# Un_51_V3_0.net
KiCad netlist of a schematic drawn in EAGLE
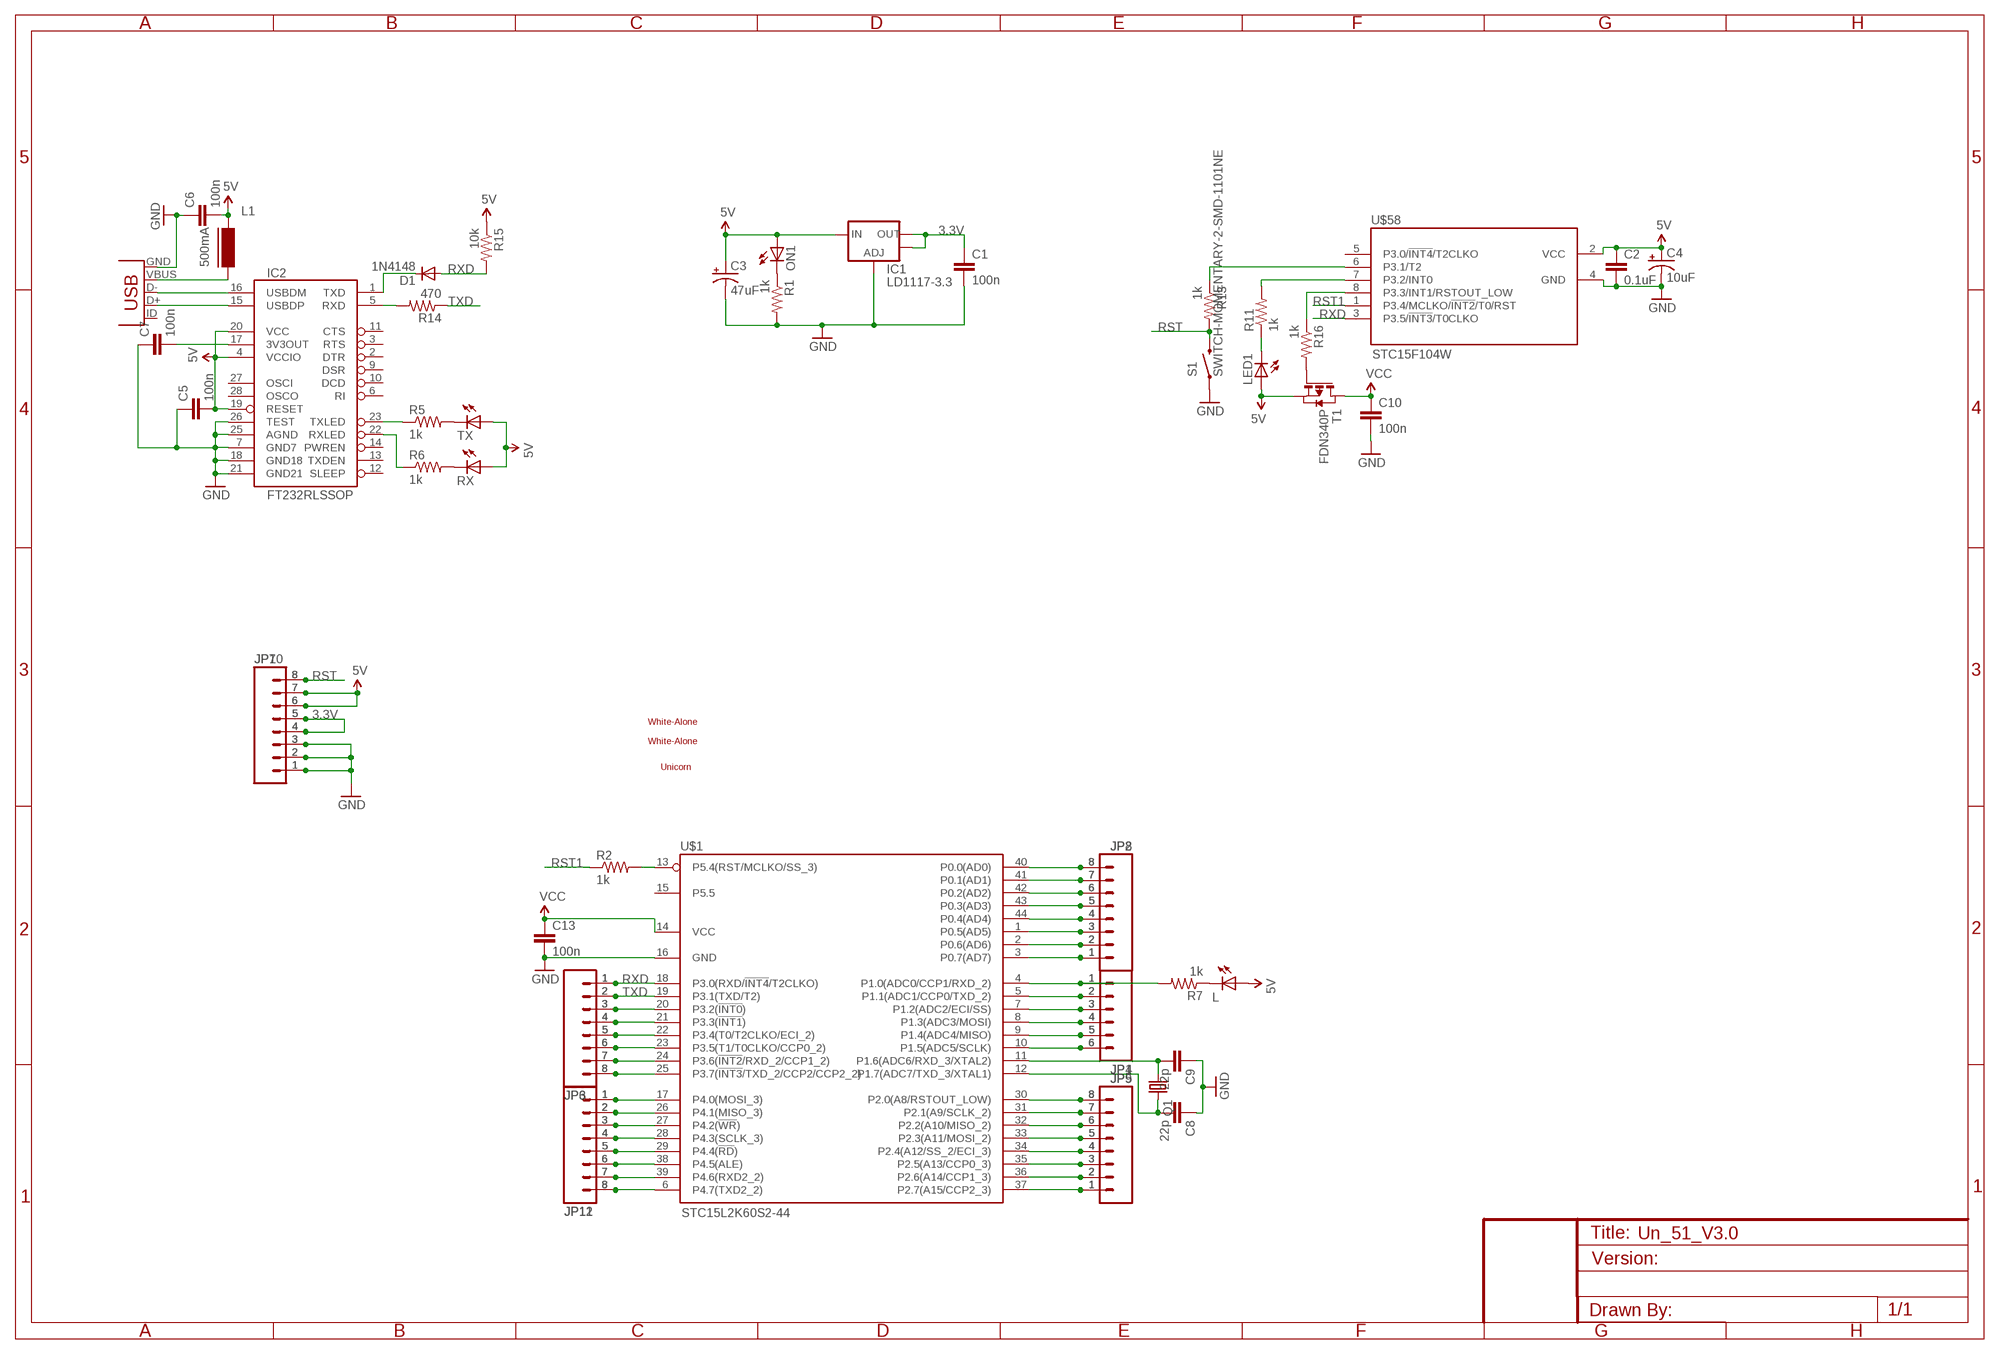
[diagram p0: schematic, sheet 1]

(export (version "E")
  (design (tool "Eeschema 10.0.6"))
  (components
    (comp (ref "C1")
      (value "100n")
      (footprint "eagle-import:0603-CAP")
      (libsource (lib "eagle-import") (part "2SparkFun_CAP0603-CAP"))
    )
    (comp (ref "C2")
      (value "0.1uF")
      (footprint "eagle-import:0603-CAP")
      (libsource (lib "eagle-import") (part "2SparkFun_CAP0603-CAP"))
    )
    (comp (ref "C3")
      (value "47uF")
      (footprint "eagle-import:PANASONIC_D")
      (libsource (lib "eagle-import") (part "CAP_POLD"))
    )
    (comp (ref "C4")
      (value "10uF")
      (footprint "eagle-import:EIA3216")
      (libsource (lib "eagle-import") (part "CAP_POL1206"))
    )
    (comp (ref "C5")
      (value "100n")
      (footprint "eagle-import:0603-CAP")
      (libsource (lib "eagle-import") (part "2SparkFun_CAP0603-CAP"))
    )
    (comp (ref "C6")
      (value "100n")
      (footprint "eagle-import:0603-CAP")
      (libsource (lib "eagle-import") (part "2SparkFun_CAP0603-CAP"))
    )
    (comp (ref "C7")
      (value "100n")
      (footprint "eagle-import:0603-CAP")
      (libsource (lib "eagle-import") (part "2SparkFun_CAP0603-CAP"))
    )
    (comp (ref "C8")
      (value "22p")
      (footprint "eagle-import:0603-CAP")
      (libsource (lib "eagle-import") (part "2SparkFun_CAP0603-CAP"))
    )
    (comp (ref "C9")
      (value "22p")
      (footprint "eagle-import:0603-CAP")
      (libsource (lib "eagle-import") (part "2SparkFun_CAP0603-CAP"))
    )
    (comp (ref "C10")
      (value "100n")
      (footprint "eagle-import:0603-CAP")
      (libsource (lib "eagle-import") (part "2SparkFun_CAP0603-CAP"))
    )
    (comp (ref "C13")
      (value "100n")
      (footprint "eagle-import:0603-CAP")
      (libsource (lib "eagle-import") (part "CAP0603-CAP"))
    )
    (comp (ref "D1")
      (value "1N4148")
      (footprint "eagle-import:SOD-323")
      (libsource (lib "eagle-import") (part "DIODESOD"))
    )
    (comp (ref "IC1")
      (value "LD1117-3.3")
      (footprint "eagle-import:SOT223")
      (libsource (lib "eagle-import") (part "V_REG_LM1117SOT223"))
    )
    (comp (ref "IC2")
      (value "FT232RLSSOP")
      (footprint "eagle-import:SSOP28DB")
      (libsource (lib "eagle-import") (part "FT232RLSSOP"))
    )
    (comp (ref "JP1")
      (value "M06SIP")
      (footprint "eagle-import:1X06")
      (libsource (lib "eagle-import") (part "M06SIP"))
    )
    (comp (ref "JP2")
      (value "M08")
      (footprint "eagle-import:1X08")
      (libsource (lib "eagle-import") (part "M08"))
    )
    (comp (ref "JP3")
      (value "M08")
      (footprint "eagle-import:1X08")
      (libsource (lib "eagle-import") (part "M08"))
    )
    (comp (ref "JP4")
      (value "M06SIP")
      (footprint "eagle-import:1X06")
      (libsource (lib "eagle-import") (part "M06SIP"))
    )
    (comp (ref "JP5")
      (value "M08")
      (footprint "eagle-import:1X08")
      (libsource (lib "eagle-import") (part "M08"))
    )
    (comp (ref "JP6")
      (value "M08")
      (footprint "eagle-import:1X08")
      (libsource (lib "eagle-import") (part "M08"))
    )
    (comp (ref "JP7")
      (value "M08")
      (footprint "eagle-import:1X08")
      (libsource (lib "eagle-import") (part "M08"))
    )
    (comp (ref "JP8")
      (value "M08")
      (footprint "eagle-import:1X08")
      (libsource (lib "eagle-import") (part "M08"))
    )
    (comp (ref "JP9")
      (value "M08")
      (footprint "eagle-import:1X08")
      (libsource (lib "eagle-import") (part "M08"))
    )
    (comp (ref "JP10")
      (value "M08")
      (footprint "eagle-import:1X08")
      (libsource (lib "eagle-import") (part "M08"))
    )
    (comp (ref "JP11")
      (value "M08")
      (footprint "eagle-import:1X08")
      (libsource (lib "eagle-import") (part "M08"))
    )
    (comp (ref "JP12")
      (value "M08")
      (footprint "eagle-import:1X08")
      (libsource (lib "eagle-import") (part "M08"))
    )
    (comp (ref "L")
      (value "LED0805")
      (footprint "eagle-import:LED-0805")
      (libsource (lib "eagle-import") (part "LED0805"))
    )
    (comp (ref "L1")
      (value "500mA")
      (footprint "eagle-import:FB805")
      (libsource (lib "eagle-import") (part "FERRITE-0805"))
    )
    (comp (ref "LED1")
      (value "LED0805")
      (footprint "eagle-import:LED-0805")
      (libsource (lib "eagle-import") (part "2SparkFun_LED0805"))
    )
    (comp (ref "ON1")
      (value "LED0805")
      (footprint "eagle-import:LED-0805")
      (libsource (lib "eagle-import") (part "LED0805"))
    )
    (comp (ref "Q1")
      (value "CRYSTALHC49US")
      (footprint "eagle-import:HC49US")
      (libsource (lib "eagle-import") (part "CRYSTALHC49US"))
    )
    (comp (ref "R1")
      (value "1k")
      (footprint "eagle-import:0603-RES")
      (libsource (lib "eagle-import") (part "RESISTOR0603-RES"))
    )
    (comp (ref "R2")
      (value "1k")
      (footprint "eagle-import:0603-RES")
      (libsource (lib "eagle-import") (part "RESISTOR0603-RES"))
    )
    (comp (ref "R5")
      (value "1k")
      (footprint "eagle-import:0603-RES")
      (libsource (lib "eagle-import") (part "RESISTOR0603-RES"))
    )
    (comp (ref "R6")
      (value "1k")
      (footprint "eagle-import:0603-RES")
      (libsource (lib "eagle-import") (part "RESISTOR0603-RES"))
    )
    (comp (ref "R7")
      (value "1k")
      (footprint "eagle-import:0603-RES")
      (libsource (lib "eagle-import") (part "RESISTOR0603-RES"))
    )
    (comp (ref "R11")
      (value "1k")
      (footprint "eagle-import:0603-RES")
      (libsource (lib "eagle-import") (part "RESISTOR0603-RES"))
    )
    (comp (ref "R13")
      (value "1k")
      (footprint "eagle-import:0603-RES")
      (libsource (lib "eagle-import") (part "RESISTOR0603-RES"))
    )
    (comp (ref "R14")
      (value "470")
      (footprint "eagle-import:0603-RES")
      (libsource (lib "eagle-import") (part "RESISTOR0603-RES"))
    )
    (comp (ref "R15")
      (value "10k")
      (footprint "eagle-import:0603-RES")
      (libsource (lib "eagle-import") (part "RESISTOR0603-RES"))
    )
    (comp (ref "R16")
      (value "1k")
      (footprint "eagle-import:0603-RES")
      (libsource (lib "eagle-import") (part "RESISTOR0603-RES"))
    )
    (comp (ref "RX")
      (value "LED0805")
      (footprint "eagle-import:LED-0805")
      (libsource (lib "eagle-import") (part "LED0805"))
    )
    (comp (ref "S1")
      (value "SWITCH-MOMENTARY-2-SMD-1101NE")
      (footprint "eagle-import:TACTILE-SWITCH-1101NE")
      (libsource (lib "eagle-import") (part "SWITCH-MOMENTARY-2-SMD-1101NE"))
    )
    (comp (ref "T1")
      (value "FDN340P")
      (footprint "eagle-import:SOT-23")
      (libsource (lib "eagle-import") (part "PMOSSOT23"))
    )
    (comp (ref "TX")
      (value "LED0805")
      (footprint "eagle-import:LED-0805")
      (libsource (lib "eagle-import") (part "LED0805"))
    )
    (comp (ref "U$1")
      (value "STC15L2K60S2-44")
      (footprint "eagle-import:TQFP44")
      (libsource (lib "eagle-import") (part "STC15L2K60S2-44"))
    )
    (comp (ref "U$3")
      (value "UNICORN_2")
      (footprint "eagle-import:UNICORN_2")
      (libsource (lib "eagle-import") (part "UNICORN_2"))
    )
    (comp (ref "U$7")
      (value "WHITE-ALONE_0")
      (footprint "eagle-import:WHITE-ALONE_0")
      (libsource (lib "eagle-import") (part "WHITE-ALONE_0"))
    )
    (comp (ref "U$11")
      (value "WHITE-ALONE_0")
      (footprint "eagle-import:WHITE-ALONE_0")
      (libsource (lib "eagle-import") (part "WHITE-ALONE_0"))
    )
    (comp (ref "U$58")
      (value "STC15F104W")
      (footprint "eagle-import:SO08")
      (libsource (lib "eagle-import") (part "STC15F104W"))
    )
    (comp (ref "X2")
      (value "USBSMD")
      (footprint "eagle-import:USB-MINIB")
      (libsource (lib "eagle-import") (part "USBSMD"))
    )
  )
  (nets
    (net (code "1") (name "/3.3V") (class "Default")
      (node (ref "C1") (pin "1") (pinfunction "1_1") (pintype "passive"))
      (node (ref "IC1") (pin "2") (pinfunction "OUT_2") (pintype "output"))
      (node (ref "IC1") (pin "4") (pinfunction "OUT_4") (pintype "output"))
      (node (ref "JP10") (pin "4") (pinfunction "4_4") (pintype "passive"))
      (node (ref "JP10") (pin "5") (pinfunction "5_5") (pintype "passive"))
      (node (ref "JP7") (pin "4") (pinfunction "4_4") (pintype "passive"))
      (node (ref "JP7") (pin "5") (pinfunction "5_5") (pintype "passive"))
    )
    (net (code "2") (name "/RST") (class "Default")
      (node (ref "JP10") (pin "8") (pinfunction "8_8") (pintype "passive"))
      (node (ref "JP7") (pin "8") (pinfunction "8_8") (pintype "passive"))
      (node (ref "R13") (pin "2") (pinfunction "2_2") (pintype "passive"))
      (node (ref "S1") (pin "P$2") (pinfunction "2_P$2") (pintype "passive"))
    )
    (net (code "3") (name "/RST1") (class "Default")
      (node (ref "R2") (pin "1") (pinfunction "1_1") (pintype "passive"))
      (node (ref "U$58") (pin "1") (pinfunction "P3.4/MCLKO/~{INT2}/T0/RST_1") (pintype "bidirectional"))
    )
    (net (code "4") (name "/RXD") (class "Default")
      (node (ref "D1") (pin "2") (pinfunction "A_2") (pintype "passive"))
      (node (ref "JP3") (pin "1") (pinfunction "1_1") (pintype "passive"))
      (node (ref "JP6") (pin "1") (pinfunction "1_1") (pintype "passive"))
      (node (ref "R15") (pin "2") (pinfunction "2_2") (pintype "passive"))
      (node (ref "U$1") (pin "18") (pinfunction "P3.0(RXD/~{INT4}/T2CLKO)_18") (pintype "bidirectional"))
      (node (ref "U$58") (pin "3") (pinfunction "P3.5/~{INT3}/T0CLKO_3") (pintype "bidirectional"))
    )
    (net (code "5") (name "/TXD") (class "Default")
      (node (ref "JP3") (pin "2") (pinfunction "2_2") (pintype "passive"))
      (node (ref "JP6") (pin "2") (pinfunction "2_2") (pintype "passive"))
      (node (ref "R14") (pin "1") (pinfunction "1_1") (pintype "passive"))
      (node (ref "U$1") (pin "19") (pinfunction "P3.1(TXD/T2)_19") (pintype "bidirectional"))
    )
    (net (code "6") (name "5V") (class "Default")
      (node (ref "C2") (pin "1") (pinfunction "1_1") (pintype "passive"))
      (node (ref "C3") (pin "+") (pinfunction "+_+") (pintype "passive"))
      (node (ref "C4") (pin "A") (pinfunction "+_A") (pintype "passive"))
      (node (ref "C5") (pin "2") (pinfunction "2_2") (pintype "passive"))
      (node (ref "C6") (pin "2") (pinfunction "2_2") (pintype "passive"))
      (node (ref "IC1") (pin "3") (pinfunction "IN_3") (pintype "input"))
      (node (ref "IC2") (pin "19") (pinfunction "RESET_19") (pintype "input"))
      (node (ref "IC2") (pin "20") (pinfunction "VCC_20") (pintype "power_in"))
      (node (ref "IC2") (pin "4") (pinfunction "VCCIO_4") (pintype "power_in"))
      (node (ref "JP10") (pin "6") (pinfunction "6_6") (pintype "passive"))
      (node (ref "JP10") (pin "7") (pinfunction "7_7") (pintype "passive"))
      (node (ref "JP7") (pin "6") (pinfunction "6_6") (pintype "passive"))
      (node (ref "JP7") (pin "7") (pinfunction "7_7") (pintype "passive"))
      (node (ref "L") (pin "1") (pinfunction "A_1") (pintype "passive"))
      (node (ref "L1") (pin "1") (pinfunction "1_1") (pintype "passive"))
      (node (ref "LED1") (pin "1") (pinfunction "A_1") (pintype "passive"))
      (node (ref "ON1") (pin "1") (pinfunction "A_1") (pintype "passive"))
      (node (ref "R15") (pin "1") (pinfunction "1_1") (pintype "passive"))
      (node (ref "RX") (pin "1") (pinfunction "A_1") (pintype "passive"))
      (node (ref "T1") (pin "2") (pinfunction "S_2") (pintype "passive"))
      (node (ref "TX") (pin "1") (pinfunction "A_1") (pintype "passive"))
      (node (ref "U$58") (pin "2") (pinfunction "VCC_2") (pintype "bidirectional"))
    )
    (net (code "7") (name "GND") (class "Default")
      (node (ref "C1") (pin "2") (pinfunction "2_2") (pintype "passive"))
      (node (ref "C10") (pin "2") (pinfunction "2_2") (pintype "passive"))
      (node (ref "C13") (pin "2") (pinfunction "2_2") (pintype "passive"))
      (node (ref "C2") (pin "2") (pinfunction "2_2") (pintype "passive"))
      (node (ref "C3") (pin "-") (pinfunction "-_-") (pintype "passive"))
      (node (ref "C4") (pin "C") (pinfunction "-_C") (pintype "passive"))
      (node (ref "C5") (pin "1") (pinfunction "1_1") (pintype "passive"))
      (node (ref "C6") (pin "1") (pinfunction "1_1") (pintype "passive"))
      (node (ref "C7") (pin "1") (pinfunction "1_1") (pintype "passive"))
      (node (ref "C8") (pin "1") (pinfunction "1_1") (pintype "passive"))
      (node (ref "C9") (pin "1") (pinfunction "1_1") (pintype "passive"))
      (node (ref "IC1") (pin "1") (pinfunction "ADJ_1") (pintype "input"))
      (node (ref "IC2") (pin "18") (pinfunction "GND18_18") (pintype "power_in"))
      (node (ref "IC2") (pin "21") (pinfunction "GND21_21") (pintype "power_in"))
      (node (ref "IC2") (pin "25") (pinfunction "AGND_25") (pintype "power_in"))
      (node (ref "IC2") (pin "26") (pinfunction "TEST_26") (pintype "input"))
      (node (ref "IC2") (pin "7") (pinfunction "GND7_7") (pintype "power_in"))
      (node (ref "JP10") (pin "1") (pinfunction "1_1") (pintype "passive"))
      (node (ref "JP10") (pin "2") (pinfunction "2_2") (pintype "passive"))
      (node (ref "JP10") (pin "3") (pinfunction "3_3") (pintype "passive"))
      (node (ref "JP7") (pin "1") (pinfunction "1_1") (pintype "passive"))
      (node (ref "JP7") (pin "2") (pinfunction "2_2") (pintype "passive"))
      (node (ref "JP7") (pin "3") (pinfunction "3_3") (pintype "passive"))
      (node (ref "R1") (pin "2") (pinfunction "2_2") (pintype "passive"))
      (node (ref "S1") (pin "P$1") (pinfunction "1_P$1") (pintype "passive"))
      (node (ref "U$1") (pin "16") (pinfunction "GND_16") (pintype "bidirectional"))
      (node (ref "U$58") (pin "4") (pinfunction "GND_4") (pintype "bidirectional"))
      (node (ref "X2") (pin "GND") (pinfunction "GND_GND") (pintype "bidirectional"))
    )
    (net (code "8") (name "Net-(D1-C)") (class "Default")
      (node (ref "D1") (pin "1") (pinfunction "C_1") (pintype "passive"))
      (node (ref "IC2") (pin "1") (pinfunction "TXD_1") (pintype "output"))
    )
    (net (code "9") (name "Net-(IC2-3V3OUT)") (class "Default")
      (node (ref "C7") (pin "2") (pinfunction "2_2") (pintype "passive"))
      (node (ref "IC2") (pin "17") (pinfunction "3V3OUT_17") (pintype "output"))
    )
    (net (code "10") (name "Net-(IC2-RXD)") (class "Default")
      (node (ref "IC2") (pin "5") (pinfunction "RXD_5") (pintype "input"))
      (node (ref "R14") (pin "2") (pinfunction "2_2") (pintype "passive"))
    )
    (net (code "11") (name "Net-(IC2-RXLED)") (class "Default")
      (node (ref "IC2") (pin "22") (pinfunction "RXLED_22") (pintype "input"))
      (node (ref "R6") (pin "1") (pinfunction "1_1") (pintype "passive"))
    )
    (net (code "12") (name "Net-(IC2-TXLED)") (class "Default")
      (node (ref "IC2") (pin "23") (pinfunction "TXLED_23") (pintype "input"))
      (node (ref "R5") (pin "1") (pinfunction "1_1") (pintype "passive"))
    )
    (net (code "13") (name "Net-(IC2-USBDM)") (class "Default")
      (node (ref "IC2") (pin "16") (pinfunction "USBDM_16") (pintype "bidirectional"))
      (node (ref "X2") (pin "D-") (pinfunction "D-_D-") (pintype "bidirectional"))
    )
    (net (code "14") (name "Net-(IC2-USBDP)") (class "Default")
      (node (ref "IC2") (pin "15") (pinfunction "USBDP_15") (pintype "bidirectional"))
      (node (ref "X2") (pin "D+") (pinfunction "D+_D+") (pintype "bidirectional"))
    )
    (net (code "15") (name "Net-(L-C)") (class "Default")
      (node (ref "L") (pin "2") (pinfunction "C_2") (pintype "passive"))
      (node (ref "R7") (pin "1") (pinfunction "1_1") (pintype "passive"))
    )
    (net (code "16") (name "Net-(L1-Pad2)") (class "Default")
      (node (ref "L1") (pin "2") (pinfunction "2_2") (pintype "passive"))
      (node (ref "X2") (pin "VBUS") (pinfunction "VBUS_VBUS") (pintype "bidirectional"))
    )
    (net (code "17") (name "Net-(LED1-C)") (class "Default")
      (node (ref "LED1") (pin "2") (pinfunction "C_2") (pintype "passive"))
      (node (ref "R11") (pin "1") (pinfunction "1_1") (pintype "passive"))
    )
    (net (code "18") (name "Net-(ON1-C)") (class "Default")
      (node (ref "ON1") (pin "2") (pinfunction "C_2") (pintype "passive"))
      (node (ref "R1") (pin "1") (pinfunction "1_1") (pintype "passive"))
    )
    (net (code "19") (name "Net-(RX-C)") (class "Default")
      (node (ref "R6") (pin "2") (pinfunction "2_2") (pintype "passive"))
      (node (ref "RX") (pin "2") (pinfunction "C_2") (pintype "passive"))
    )
    (net (code "20") (name "Net-(T1-G)") (class "Default")
      (node (ref "R16") (pin "2") (pinfunction "2_2") (pintype "passive"))
      (node (ref "T1") (pin "3") (pinfunction "G_3") (pintype "passive"))
    )
    (net (code "21") (name "Net-(TX-C)") (class "Default")
      (node (ref "R5") (pin "2") (pinfunction "2_2") (pintype "passive"))
      (node (ref "TX") (pin "2") (pinfunction "C_2") (pintype "passive"))
    )
    (net (code "22") (name "Net-(U$1-P0.0(AD0))") (class "Default")
      (node (ref "JP2") (pin "8") (pinfunction "8_8") (pintype "passive"))
      (node (ref "JP8") (pin "8") (pinfunction "8_8") (pintype "passive"))
      (node (ref "U$1") (pin "40") (pinfunction "P0.0(AD0)_40") (pintype "bidirectional"))
    )
    (net (code "23") (name "Net-(U$1-P0.1(AD1))") (class "Default")
      (node (ref "JP2") (pin "7") (pinfunction "7_7") (pintype "passive"))
      (node (ref "JP8") (pin "7") (pinfunction "7_7") (pintype "passive"))
      (node (ref "U$1") (pin "41") (pinfunction "P0.1(AD1)_41") (pintype "bidirectional"))
    )
    (net (code "24") (name "Net-(U$1-P0.2(AD2))") (class "Default")
      (node (ref "JP2") (pin "6") (pinfunction "6_6") (pintype "passive"))
      (node (ref "JP8") (pin "6") (pinfunction "6_6") (pintype "passive"))
      (node (ref "U$1") (pin "42") (pinfunction "P0.2(AD2)_42") (pintype "bidirectional"))
    )
    (net (code "25") (name "Net-(U$1-P0.3(AD3))") (class "Default")
      (node (ref "JP2") (pin "5") (pinfunction "5_5") (pintype "passive"))
      (node (ref "JP8") (pin "5") (pinfunction "5_5") (pintype "passive"))
      (node (ref "U$1") (pin "43") (pinfunction "P0.3(AD3)_43") (pintype "bidirectional"))
    )
    (net (code "26") (name "Net-(U$1-P0.4(AD4))") (class "Default")
      (node (ref "JP2") (pin "4") (pinfunction "4_4") (pintype "passive"))
      (node (ref "JP8") (pin "4") (pinfunction "4_4") (pintype "passive"))
      (node (ref "U$1") (pin "44") (pinfunction "P0.4(AD4)_44") (pintype "bidirectional"))
    )
    (net (code "27") (name "Net-(U$1-P0.5(AD5))") (class "Default")
      (node (ref "JP2") (pin "3") (pinfunction "3_3") (pintype "passive"))
      (node (ref "JP8") (pin "3") (pinfunction "3_3") (pintype "passive"))
      (node (ref "U$1") (pin "1") (pinfunction "P0.5(AD5)_1") (pintype "bidirectional"))
    )
    (net (code "28") (name "Net-(U$1-P0.6(AD6))") (class "Default")
      (node (ref "JP2") (pin "2") (pinfunction "2_2") (pintype "passive"))
      (node (ref "JP8") (pin "2") (pinfunction "2_2") (pintype "passive"))
      (node (ref "U$1") (pin "2") (pinfunction "P0.6(AD6)_2") (pintype "bidirectional"))
    )
    (net (code "29") (name "Net-(U$1-P0.7(AD7))") (class "Default")
      (node (ref "JP2") (pin "1") (pinfunction "1_1") (pintype "passive"))
      (node (ref "JP8") (pin "1") (pinfunction "1_1") (pintype "passive"))
      (node (ref "U$1") (pin "3") (pinfunction "P0.7(AD7)_3") (pintype "bidirectional"))
    )
    (net (code "30") (name "Net-(U$1-P1.0(ADC0{slash}CCP1{slash}RXD_2))") (class "Default")
      (node (ref "JP1") (pin "1") (pinfunction "1_1") (pintype "passive"))
      (node (ref "JP4") (pin "1") (pinfunction "1_1") (pintype "passive"))
      (node (ref "R7") (pin "2") (pinfunction "2_2") (pintype "passive"))
      (node (ref "U$1") (pin "4") (pinfunction "P1.0(ADC0/CCP1/RXD_2)_4") (pintype "bidirectional"))
    )
    (net (code "31") (name "Net-(U$1-P1.1(ADC1{slash}CCP0{slash}TXD_2))") (class "Default")
      (node (ref "JP1") (pin "2") (pinfunction "2_2") (pintype "passive"))
      (node (ref "JP4") (pin "2") (pinfunction "2_2") (pintype "passive"))
      (node (ref "U$1") (pin "5") (pinfunction "P1.1(ADC1/CCP0/TXD_2)_5") (pintype "bidirectional"))
    )
    (net (code "32") (name "Net-(U$1-P1.2(ADC2{slash}ECI{slash}SS))") (class "Default")
      (node (ref "JP1") (pin "3") (pinfunction "3_3") (pintype "passive"))
      (node (ref "JP4") (pin "3") (pinfunction "3_3") (pintype "passive"))
      (node (ref "U$1") (pin "7") (pinfunction "P1.2(ADC2/ECI/SS)_7") (pintype "bidirectional"))
    )
    (net (code "33") (name "Net-(U$1-P1.3(ADC3{slash}MOSI))") (class "Default")
      (node (ref "JP1") (pin "4") (pinfunction "4_4") (pintype "passive"))
      (node (ref "JP4") (pin "4") (pinfunction "4_4") (pintype "passive"))
      (node (ref "U$1") (pin "8") (pinfunction "P1.3(ADC3/MOSI)_8") (pintype "bidirectional"))
    )
    (net (code "34") (name "Net-(U$1-P1.4(ADC4{slash}MISO))") (class "Default")
      (node (ref "JP1") (pin "5") (pinfunction "5_5") (pintype "passive"))
      (node (ref "JP4") (pin "5") (pinfunction "5_5") (pintype "passive"))
      (node (ref "U$1") (pin "9") (pinfunction "P1.4(ADC4/MISO)_9") (pintype "bidirectional"))
    )
    (net (code "35") (name "Net-(U$1-P1.5(ADC5{slash}SCLK))") (class "Default")
      (node (ref "JP1") (pin "6") (pinfunction "6_6") (pintype "passive"))
      (node (ref "JP4") (pin "6") (pinfunction "6_6") (pintype "passive"))
      (node (ref "U$1") (pin "10") (pinfunction "P1.5(ADC5/SCLK)_10") (pintype "bidirectional"))
    )
    (net (code "36") (name "Net-(U$1-P1.6(ADC6{slash}RXD_3{slash}XTAL2))") (class "Default")
      (node (ref "C9") (pin "2") (pinfunction "2_2") (pintype "passive"))
      (node (ref "Q1") (pin "1") (pinfunction "1_1") (pintype "passive"))
      (node (ref "U$1") (pin "11") (pinfunction "P1.6(ADC6/RXD_3/XTAL2)_11") (pintype "bidirectional"))
    )
    (net (code "37") (name "Net-(U$1-P1.7(ADC7{slash}TXD_3{slash}XTAL1))") (class "Default")
      (node (ref "C8") (pin "2") (pinfunction "2_2") (pintype "passive"))
      (node (ref "Q1") (pin "2") (pinfunction "2_2") (pintype "passive"))
      (node (ref "U$1") (pin "12") (pinfunction "P1.7(ADC7/TXD_3/XTAL1)_12") (pintype "bidirectional"))
    )
    (net (code "38") (name "Net-(U$1-P2.0(A8{slash}RSTOUT_LOW))") (class "Default")
      (node (ref "JP5") (pin "8") (pinfunction "8_8") (pintype "passive"))
      (node (ref "JP9") (pin "8") (pinfunction "8_8") (pintype "passive"))
      (node (ref "U$1") (pin "30") (pinfunction "P2.0(A8/RSTOUT_LOW)_30") (pintype "bidirectional"))
    )
    (net (code "39") (name "Net-(U$1-P2.1(A9{slash}SCLK_2))") (class "Default")
      (node (ref "JP5") (pin "7") (pinfunction "7_7") (pintype "passive"))
      (node (ref "JP9") (pin "7") (pinfunction "7_7") (pintype "passive"))
      (node (ref "U$1") (pin "31") (pinfunction "P2.1(A9/SCLK_2)_31") (pintype "bidirectional"))
    )
    (net (code "40") (name "Net-(U$1-P2.2(A10{slash}MISO_2))") (class "Default")
      (node (ref "JP5") (pin "6") (pinfunction "6_6") (pintype "passive"))
      (node (ref "JP9") (pin "6") (pinfunction "6_6") (pintype "passive"))
      (node (ref "U$1") (pin "32") (pinfunction "P2.2(A10/MISO_2)_32") (pintype "bidirectional"))
    )
    (net (code "41") (name "Net-(U$1-P2.3(A11{slash}MOSI_2))") (class "Default")
      (node (ref "JP5") (pin "5") (pinfunction "5_5") (pintype "passive"))
      (node (ref "JP9") (pin "5") (pinfunction "5_5") (pintype "passive"))
      (node (ref "U$1") (pin "33") (pinfunction "P2.3(A11/MOSI_2)_33") (pintype "bidirectional"))
    )
    (net (code "42") (name "Net-(U$1-P2.4(A12{slash}SS_2{slash}ECI_3))") (class "Default")
      (node (ref "JP5") (pin "4") (pinfunction "4_4") (pintype "passive"))
      (node (ref "JP9") (pin "4") (pinfunction "4_4") (pintype "passive"))
      (node (ref "U$1") (pin "34") (pinfunction "P2.4(A12/SS_2/ECI_3)_34") (pintype "bidirectional"))
    )
    (net (code "43") (name "Net-(U$1-P2.5(A13{slash}CCP0_3))") (class "Default")
      (node (ref "JP5") (pin "3") (pinfunction "3_3") (pintype "passive"))
      (node (ref "JP9") (pin "3") (pinfunction "3_3") (pintype "passive"))
      (node (ref "U$1") (pin "35") (pinfunction "P2.5(A13/CCP0_3)_35") (pintype "bidirectional"))
    )
    (net (code "44") (name "Net-(U$1-P2.6(A14{slash}CCP1_3))") (class "Default")
      (node (ref "JP5") (pin "2") (pinfunction "2_2") (pintype "passive"))
      (node (ref "JP9") (pin "2") (pinfunction "2_2") (pintype "passive"))
      (node (ref "U$1") (pin "36") (pinfunction "P2.6(A14/CCP1_3)_36") (pintype "bidirectional"))
    )
    (net (code "45") (name "Net-(U$1-P2.7(A15{slash}CCP2_3))") (class "Default")
      (node (ref "JP5") (pin "1") (pinfunction "1_1") (pintype "passive"))
      (node (ref "JP9") (pin "1") (pinfunction "1_1") (pintype "passive"))
      (node (ref "U$1") (pin "37") (pinfunction "P2.7(A15/CCP2_3)_37") (pintype "bidirectional"))
    )
    (net (code "46") (name "Net-(U$1-P3.2(~{INT0}))") (class "Default")
      (node (ref "JP3") (pin "3") (pinfunction "3_3") (pintype "passive"))
      (node (ref "JP6") (pin "3") (pinfunction "3_3") (pintype "passive"))
      (node (ref "U$1") (pin "20") (pinfunction "P3.2(~{INT0})_20") (pintype "bidirectional"))
    )
    (net (code "47") (name "Net-(U$1-P3.3(~{INT1}))") (class "Default")
      (node (ref "JP3") (pin "4") (pinfunction "4_4") (pintype "passive"))
      (node (ref "JP6") (pin "4") (pinfunction "4_4") (pintype "passive"))
      (node (ref "U$1") (pin "21") (pinfunction "P3.3(~{INT1})_21") (pintype "bidirectional"))
    )
    (net (code "48") (name "Net-(U$1-P3.4(T0{slash}T2CLKO{slash}ECI_2))") (class "Default")
      (node (ref "JP3") (pin "5") (pinfunction "5_5") (pintype "passive"))
      (node (ref "JP6") (pin "5") (pinfunction "5_5") (pintype "passive"))
      (node (ref "U$1") (pin "22") (pinfunction "P3.4(T0/T2CLKO/ECI_2)_22") (pintype "bidirectional"))
    )
    (net (code "49") (name "Net-(U$1-P3.5(T1{slash}T0CLKO{slash}CCP0_2))") (class "Default")
      (node (ref "JP3") (pin "6") (pinfunction "6_6") (pintype "passive"))
      (node (ref "JP6") (pin "6") (pinfunction "6_6") (pintype "passive"))
      (node (ref "U$1") (pin "23") (pinfunction "P3.5(T1/T0CLKO/CCP0_2)_23") (pintype "bidirectional"))
    )
    (net (code "50") (name "Net-(U$1-P3.6(~{INT2}{slash}RXD_2{slash}CCP1_2))") (class "Default")
      (node (ref "JP3") (pin "7") (pinfunction "7_7") (pintype "passive"))
      (node (ref "JP6") (pin "7") (pinfunction "7_7") (pintype "passive"))
      (node (ref "U$1") (pin "24") (pinfunction "P3.6(~{INT2}/RXD_2/CCP1_2)_24") (pintype "bidirectional"))
    )
    (net (code "51") (name "Net-(U$1-P3.7(~{INT3}{slash}TXD_2{slash}CCP2{slash}CCP2_2))") (class "Default")
      (node (ref "JP3") (pin "8") (pinfunction "8_8") (pintype "passive"))
      (node (ref "JP6") (pin "8") (pinfunction "8_8") (pintype "passive"))
      (node (ref "U$1") (pin "25") (pinfunction "P3.7(~{INT3}/TXD_2/CCP2/CCP2_2)_25") (pintype "bidirectional"))
    )
    (net (code "52") (name "Net-(U$1-P4.0(MOSI_3))") (class "Default")
      (node (ref "JP11") (pin "1") (pinfunction "1_1") (pintype "passive"))
      (node (ref "JP12") (pin "1") (pinfunction "1_1") (pintype "passive"))
      (node (ref "U$1") (pin "17") (pinfunction "P4.0(MOSI_3)_17") (pintype "bidirectional"))
    )
    (net (code "53") (name "Net-(U$1-P4.1(MISO_3))") (class "Default")
      (node (ref "JP11") (pin "2") (pinfunction "2_2") (pintype "passive"))
      (node (ref "JP12") (pin "2") (pinfunction "2_2") (pintype "passive"))
      (node (ref "U$1") (pin "26") (pinfunction "P4.1(MISO_3)_26") (pintype "bidirectional"))
    )
    (net (code "54") (name "Net-(U$1-P4.2(~{WR}))") (class "Default")
      (node (ref "JP11") (pin "3") (pinfunction "3_3") (pintype "passive"))
      (node (ref "JP12") (pin "3") (pinfunction "3_3") (pintype "passive"))
      (node (ref "U$1") (pin "27") (pinfunction "P4.2(~{WR})_27") (pintype "bidirectional"))
    )
    (net (code "55") (name "Net-(U$1-P4.3(SCLK_3))") (class "Default")
      (node (ref "JP11") (pin "4") (pinfunction "4_4") (pintype "passive"))
      (node (ref "JP12") (pin "4") (pinfunction "4_4") (pintype "passive"))
      (node (ref "U$1") (pin "28") (pinfunction "P4.3(SCLK_3)_28") (pintype "bidirectional"))
    )
    (net (code "56") (name "Net-(U$1-P4.4(~{RD}))") (class "Default")
      (node (ref "JP11") (pin "5") (pinfunction "5_5") (pintype "passive"))
      (node (ref "JP12") (pin "5") (pinfunction "5_5") (pintype "passive"))
      (node (ref "U$1") (pin "29") (pinfunction "P4.4(~{RD})_29") (pintype "bidirectional"))
    )
    (net (code "57") (name "Net-(U$1-P4.5(ALE))") (class "Default")
      (node (ref "JP11") (pin "6") (pinfunction "6_6") (pintype "passive"))
      (node (ref "JP12") (pin "6") (pinfunction "6_6") (pintype "passive"))
      (node (ref "U$1") (pin "38") (pinfunction "P4.5(ALE)_38") (pintype "bidirectional"))
    )
    (net (code "58") (name "Net-(U$1-P4.6(RXD2_2))") (class "Default")
      (node (ref "JP11") (pin "7") (pinfunction "7_7") (pintype "passive"))
      (node (ref "JP12") (pin "7") (pinfunction "7_7") (pintype "passive"))
      (node (ref "U$1") (pin "39") (pinfunction "P4.6(RXD2_2)_39") (pintype "bidirectional"))
    )
    (net (code "59") (name "Net-(U$1-P4.7(TXD2_2))") (class "Default")
      (node (ref "JP11") (pin "8") (pinfunction "8_8") (pintype "passive"))
      (node (ref "JP12") (pin "8") (pinfunction "8_8") (pintype "passive"))
      (node (ref "U$1") (pin "6") (pinfunction "P4.7(TXD2_2)_6") (pintype "bidirectional"))
    )
    (net (code "60") (name "Net-(U$1-P5.4(RST{slash}MCLKO{slash}SS_3))") (class "Default")
      (node (ref "R2") (pin "2") (pinfunction "2_2") (pintype "passive"))
      (node (ref "U$1") (pin "13") (pinfunction "P5.4(RST/MCLKO/SS_3)_13") (pintype "bidirectional"))
    )
    (net (code "61") (name "Net-(U$58-P3.1{slash}T2)") (class "Default")
      (node (ref "R13") (pin "1") (pinfunction "1_1") (pintype "passive"))
      (node (ref "U$58") (pin "6") (pinfunction "P3.1/T2_6") (pintype "bidirectional"))
    )
    (net (code "62") (name "Net-(U$58-P3.2{slash}INT0)") (class "Default")
      (node (ref "R11") (pin "2") (pinfunction "2_2") (pintype "passive"))
      (node (ref "U$58") (pin "7") (pinfunction "P3.2/INT0_7") (pintype "bidirectional"))
    )
    (net (code "63") (name "Net-(U$58-P3.3{slash}INT1{slash}RSTOUT_LOW)") (class "Default")
      (node (ref "R16") (pin "1") (pinfunction "1_1") (pintype "passive"))
      (node (ref "U$58") (pin "8") (pinfunction "P3.3/INT1/RSTOUT_LOW_8") (pintype "bidirectional"))
    )
    (net (code "64") (name "VCC") (class "Default")
      (node (ref "C10") (pin "1") (pinfunction "1_1") (pintype "passive"))
      (node (ref "C13") (pin "1") (pinfunction "1_1") (pintype "passive"))
      (node (ref "T1") (pin "1") (pinfunction "D_1") (pintype "passive"))
      (node (ref "U$1") (pin "14") (pinfunction "VCC_14") (pintype "bidirectional"))
    )
    (net (code "65") (name "unconnected-(IC2-CTS-Pad11)") (class "Default")
      (node (ref "IC2") (pin "11") (pinfunction "CTS_11") (pintype "input"))
    )
    (net (code "66") (name "unconnected-(IC2-DCD-Pad10)") (class "Default")
      (node (ref "IC2") (pin "10") (pinfunction "DCD_10") (pintype "input"))
    )
    (net (code "67") (name "unconnected-(IC2-DSR-Pad9)") (class "Default")
      (node (ref "IC2") (pin "9") (pinfunction "DSR_9") (pintype "input"))
    )
    (net (code "68") (name "unconnected-(IC2-DTR-Pad2)") (class "Default")
      (node (ref "IC2") (pin "2") (pinfunction "DTR_2") (pintype "output"))
    )
    (net (code "69") (name "unconnected-(IC2-OSCI-Pad27)") (class "Default")
      (node (ref "IC2") (pin "27") (pinfunction "OSCI_27") (pintype "input"))
    )
    (net (code "70") (name "unconnected-(IC2-OSCO-Pad28)") (class "Default")
      (node (ref "IC2") (pin "28") (pinfunction "OSCO_28") (pintype "output"))
    )
    (net (code "71") (name "unconnected-(IC2-PWREN-Pad14)") (class "Default")
      (node (ref "IC2") (pin "14") (pinfunction "PWREN_14") (pintype "input"))
    )
    (net (code "72") (name "unconnected-(IC2-RI-Pad6)") (class "Default")
      (node (ref "IC2") (pin "6") (pinfunction "RI_6") (pintype "input"))
    )
    (net (code "73") (name "unconnected-(IC2-RTS-Pad3)") (class "Default")
      (node (ref "IC2") (pin "3") (pinfunction "RTS_3") (pintype "output"))
    )
    (net (code "74") (name "unconnected-(IC2-SLEEP-Pad12)") (class "Default")
      (node (ref "IC2") (pin "12") (pinfunction "SLEEP_12") (pintype "input"))
    )
    (net (code "75") (name "unconnected-(IC2-TXDEN-Pad13)") (class "Default")
      (node (ref "IC2") (pin "13") (pinfunction "TXDEN_13") (pintype "input"))
    )
    (net (code "76") (name "unconnected-(U$1-P5.5-Pad15)") (class "Default")
      (node (ref "U$1") (pin "15") (pinfunction "P5.5_15") (pintype "bidirectional"))
    )
    (net (code "77") (name "unconnected-(U$58-P3.0{slash}~{INT4}{slash}T2CLKO-Pad5)") (class "Default")
      (node (ref "U$58") (pin "5") (pinfunction "P3.0/~{INT4}/T2CLKO_5") (pintype "bidirectional"))
    )
    (net (code "78") (name "unconnected-(X2-USBID-PadID)") (class "Default")
      (node (ref "X2") (pin "ID") (pinfunction "USBID_ID") (pintype "bidirectional"))
    )
  )
)
